# diskohedron4w_pinheaders.net
KiCad netlist of a schematic drawn in EAGLE
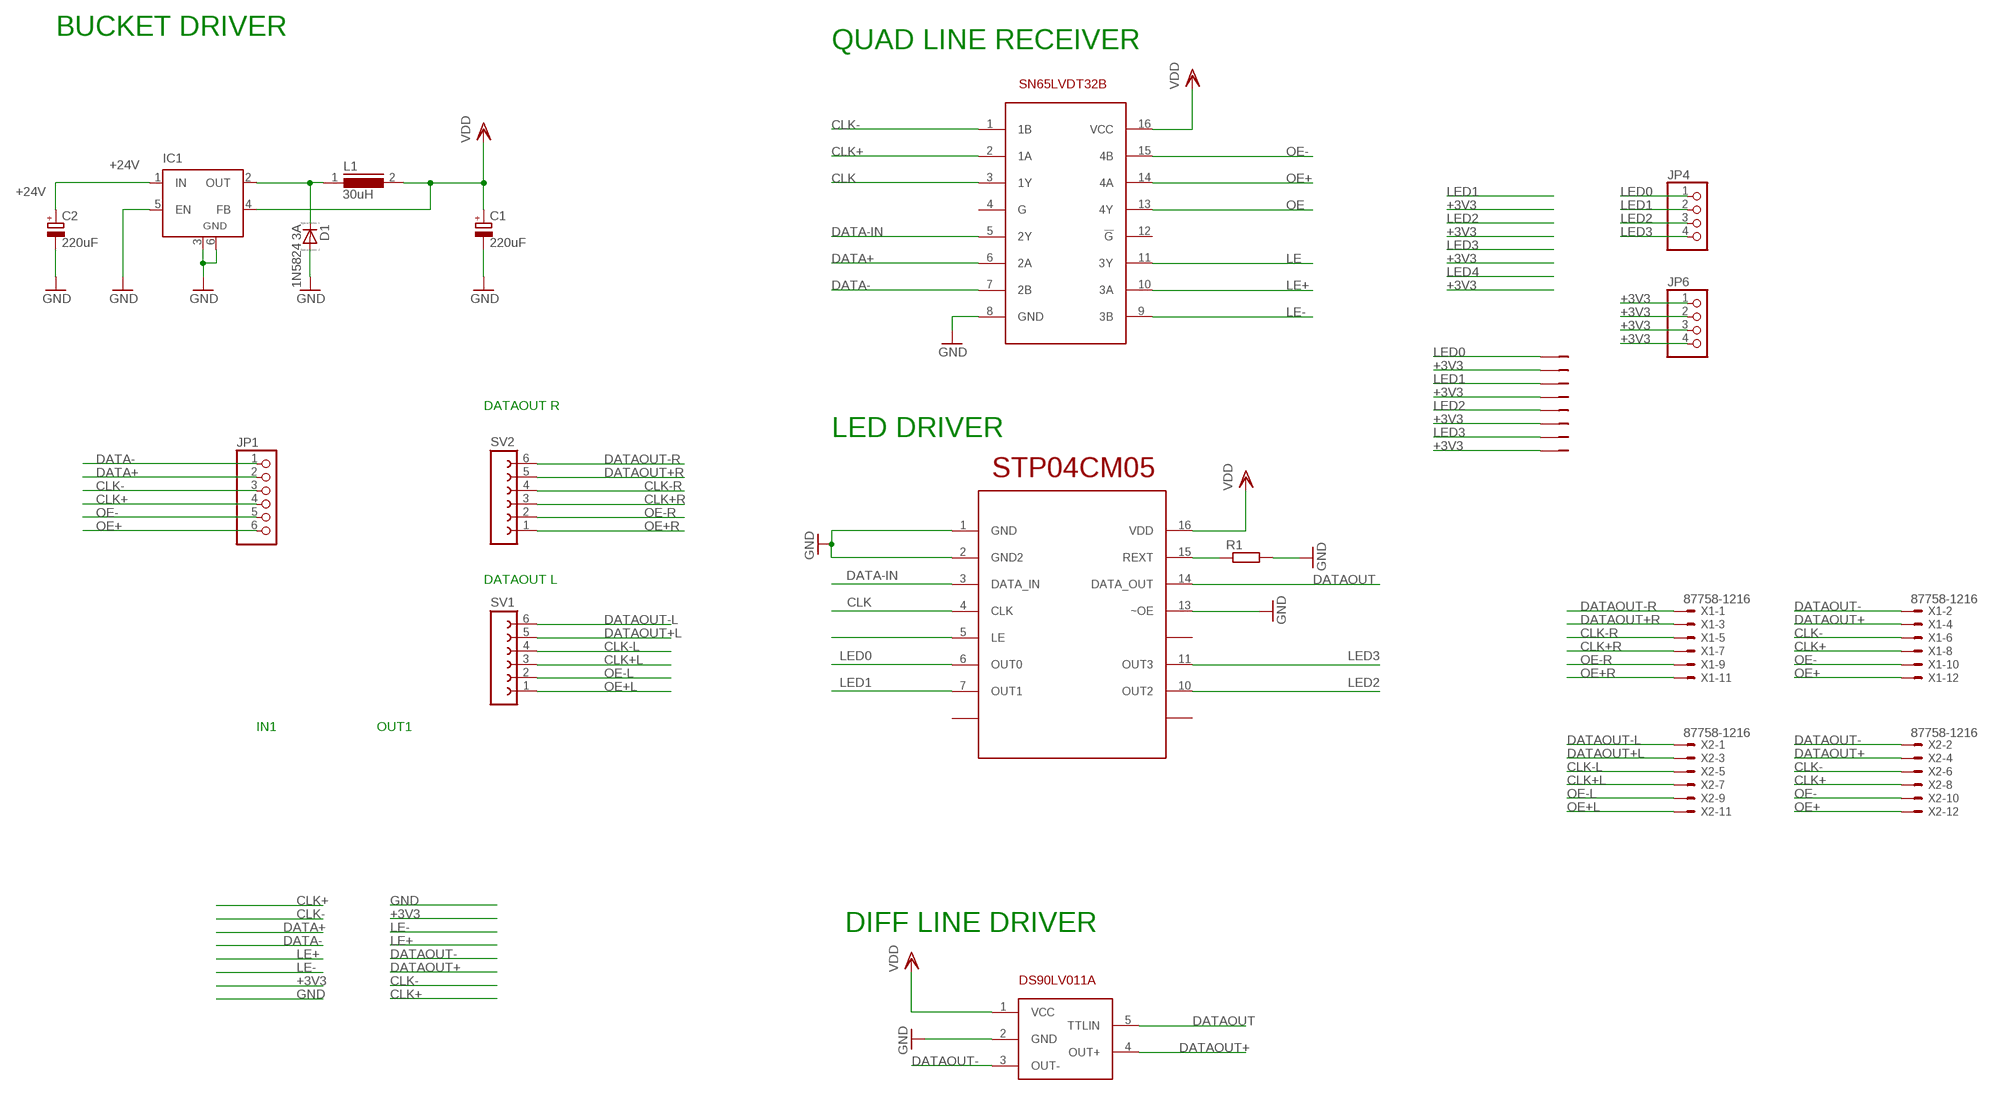
[diagram p0: schematic, sheet 1]

(export (version "E")
  (design (tool "Eeschema 10.0.6"))
  (components
    (comp (ref "C1")
      (value "220uF")
      (footprint "eagle-import:153CLV-1010")
      (libsource (lib "eagle-import") (part "CPOL-EU153CLV-1010"))
    )
    (comp (ref "C2")
      (value "220uF")
      (footprint "eagle-import:153CLV-1010")
      (libsource (lib "eagle-import") (part "CPOL-EU153CLV-1010"))
    )
    (comp (ref "D1")
      (value "1N5824 3A")
      (footprint "eagle-import:DIODE_SMC")
      (libsource (lib "eagle-import") (part "DIODE_E-SMC"))
    )
    (comp (ref "IC1")
      (value "LM2596S")
      (footprint "eagle-import:TO263-5")
      (libsource (lib "eagle-import") (part "LM2596S"))
    )
    (comp (ref "JP1")
      (value "PINHD-1X06_2.54-90°")
      (footprint "eagle-import:1X06_90")
      (libsource (lib "eagle-import") (part "PINHD-1X06_2.54-90°"))
    )
    (comp (ref "JP4")
      (value "PINHD-1X4")
      (footprint "eagle-import:1X04")
      (libsource (lib "eagle-import") (part "PINHD-1X4"))
    )
    (comp (ref "JP6")
      (value "PINHD-1X4")
      (footprint "eagle-import:1X04")
      (libsource (lib "eagle-import") (part "PINHD-1X4"))
    )
    (comp (ref "L1")
      (value "30uH")
      (footprint "eagle-import:DR127")
      (libsource (lib "eagle-import") (part "DR127"))
    )
    (comp (ref "R1")
      (value "R-EU_M0805")
      (footprint "eagle-import:M0805")
      (libsource (lib "eagle-import") (part "R-EU_M0805"))
    )
    (comp (ref "SV1")
      (value "FE06W")
      (footprint "eagle-import:FE06W")
      (libsource (lib "eagle-import") (part "FE06W"))
    )
    (comp (ref "SV2")
      (value "FE06W")
      (footprint "eagle-import:FE06W")
      (libsource (lib "eagle-import") (part "FE06W"))
    )
    (comp (ref "U$1")
      (value "STP04CM05")
      (footprint "eagle-import:TSSOP16")
      (libsource (lib "eagle-import") (part "STP04CM05"))
    )
    (comp (ref "U$2")
      (value "SN65LVDST32")
      (footprint "eagle-import:SOIC16")
      (libsource (lib "eagle-import") (part "SN65LVDST32"))
    )
    (comp (ref "U$3")
      (value "DS90LV011A")
      (footprint "eagle-import:SOT23-5")
      (libsource (lib "eagle-import") (part "DS90LV011A"))
    )
    (comp (ref "U$4")
      (value "8PIN-ZH")
      (footprint "eagle-import:B8B-ZH")
      (libsource (lib "eagle-import") (part "8PIN-ZH"))
    )
    (comp (ref "X1")
      (value "87758-1216")
      (footprint "eagle-import:87758-1216")
      (libsource (lib "eagle-import") (part "87758-1216"))
    )
    (comp (ref "X2")
      (value "87758-1216")
      (footprint "eagle-import:87758-1216")
      (libsource (lib "eagle-import") (part "87758-1216"))
    )
  )
  (nets
    (net (code "1") (name "/+24V") (class "Default")
      (node (ref "C2") (pin "+") (pinfunction "+_+") (pintype "passive"))
      (node (ref "IC1") (pin "1") (pinfunction "IN_1") (pintype "input"))
    )
    (net (code "2") (name "/CLK") (class "Default")
      (node (ref "U$1") (pin "4") (pinfunction "CLK_4") (pintype "bidirectional"))
      (node (ref "U$2") (pin "3") (pinfunction "1Y_3") (pintype "bidirectional"))
    )
    (net (code "3") (name "/CLK+") (class "Default")
      (node (ref "JP1") (pin "4") (pinfunction "4_4") (pintype "passive"))
      (node (ref "U$2") (pin "2") (pinfunction "1A_2") (pintype "bidirectional"))
      (node (ref "X1") (pin "8") (pinfunction "S_8") (pintype "passive"))
      (node (ref "X2") (pin "8") (pinfunction "S_8") (pintype "passive"))
    )
    (net (code "4") (name "/CLK+L") (class "Default")
      (node (ref "SV1") (pin "3") (pinfunction "3_3") (pintype "passive"))
      (node (ref "X2") (pin "7") (pinfunction "S_7") (pintype "passive"))
    )
    (net (code "5") (name "/CLK+R") (class "Default")
      (node (ref "SV2") (pin "3") (pinfunction "3_3") (pintype "passive"))
      (node (ref "X1") (pin "7") (pinfunction "S_7") (pintype "passive"))
    )
    (net (code "6") (name "/CLK-") (class "Default")
      (node (ref "JP1") (pin "3") (pinfunction "3_3") (pintype "passive"))
      (node (ref "U$2") (pin "1") (pinfunction "1B_1") (pintype "bidirectional"))
      (node (ref "X1") (pin "6") (pinfunction "S_6") (pintype "passive"))
      (node (ref "X2") (pin "6") (pinfunction "S_6") (pintype "passive"))
    )
    (net (code "7") (name "/CLK-L") (class "Default")
      (node (ref "SV1") (pin "4") (pinfunction "4_4") (pintype "passive"))
      (node (ref "X2") (pin "5") (pinfunction "S_5") (pintype "passive"))
    )
    (net (code "8") (name "/CLK-R") (class "Default")
      (node (ref "SV2") (pin "4") (pinfunction "4_4") (pintype "passive"))
      (node (ref "X1") (pin "5") (pinfunction "S_5") (pintype "passive"))
    )
    (net (code "9") (name "/DATA+") (class "Default")
      (node (ref "JP1") (pin "2") (pinfunction "2_2") (pintype "passive"))
      (node (ref "U$2") (pin "6") (pinfunction "2A_6") (pintype "bidirectional"))
    )
    (net (code "10") (name "/DATA-") (class "Default")
      (node (ref "JP1") (pin "1") (pinfunction "1_1") (pintype "passive"))
      (node (ref "U$2") (pin "7") (pinfunction "2B_7") (pintype "bidirectional"))
    )
    (net (code "11") (name "/DATA-IN") (class "Default")
      (node (ref "U$1") (pin "3") (pinfunction "DATA_IN_3") (pintype "bidirectional"))
      (node (ref "U$2") (pin "5") (pinfunction "2Y_5") (pintype "bidirectional"))
    )
    (net (code "12") (name "/DATAOUT") (class "Default")
      (node (ref "U$1") (pin "14") (pinfunction "DATA_OUT_14") (pintype "bidirectional"))
      (node (ref "U$3") (pin "5") (pinfunction "TTLIN_5") (pintype "bidirectional"))
    )
    (net (code "13") (name "/DATAOUT+") (class "Default")
      (node (ref "U$3") (pin "4") (pinfunction "OUT+_4") (pintype "bidirectional"))
      (node (ref "X1") (pin "4") (pinfunction "S_4") (pintype "passive"))
      (node (ref "X2") (pin "4") (pinfunction "S_4") (pintype "passive"))
    )
    (net (code "14") (name "/DATAOUT+L") (class "Default")
      (node (ref "SV1") (pin "5") (pinfunction "5_5") (pintype "passive"))
      (node (ref "X2") (pin "3") (pinfunction "S_3") (pintype "passive"))
    )
    (net (code "15") (name "/DATAOUT+R") (class "Default")
      (node (ref "SV2") (pin "5") (pinfunction "5_5") (pintype "passive"))
      (node (ref "X1") (pin "3") (pinfunction "S_3") (pintype "passive"))
    )
    (net (code "16") (name "/DATAOUT-") (class "Default")
      (node (ref "U$3") (pin "3") (pinfunction "OUT-_3") (pintype "bidirectional"))
      (node (ref "X1") (pin "2") (pinfunction "S_2") (pintype "passive"))
      (node (ref "X2") (pin "2") (pinfunction "S_2") (pintype "passive"))
    )
    (net (code "17") (name "/DATAOUT-L") (class "Default")
      (node (ref "SV1") (pin "6") (pinfunction "6_6") (pintype "passive"))
      (node (ref "X2") (pin "1") (pinfunction "S_1") (pintype "passive"))
    )
    (net (code "18") (name "/DATAOUT-R") (class "Default")
      (node (ref "SV2") (pin "6") (pinfunction "6_6") (pintype "passive"))
      (node (ref "X1") (pin "1") (pinfunction "S_1") (pintype "passive"))
    )
    (net (code "19") (name "/LE") (class "Default")
      (node (ref "U$1") (pin "5") (pinfunction "LE_5") (pintype "bidirectional"))
      (node (ref "U$2") (pin "11") (pinfunction "3Y_11") (pintype "bidirectional"))
    )
    (net (code "20") (name "/LE+") (class "Default")
      (node (ref "U$2") (pin "10") (pinfunction "3A_10") (pintype "bidirectional"))
    )
    (net (code "21") (name "/LE-") (class "Default")
      (node (ref "U$2") (pin "9") (pinfunction "3B_9") (pintype "bidirectional"))
    )
    (net (code "22") (name "/LED0") (class "Default")
      (node (ref "JP4") (pin "1") (pinfunction "1_1") (pintype "passive"))
      (node (ref "U$1") (pin "6") (pinfunction "OUT0_6") (pintype "bidirectional"))
      (node (ref "U$4") (pin "1") (pinfunction "1_1") (pintype "passive"))
    )
    (net (code "23") (name "/LED1") (class "Default")
      (node (ref "JP4") (pin "2") (pinfunction "2_2") (pintype "passive"))
      (node (ref "U$1") (pin "7") (pinfunction "OUT1_7") (pintype "bidirectional"))
      (node (ref "U$4") (pin "3") (pinfunction "1_3") (pintype "passive"))
    )
    (net (code "24") (name "/LED2") (class "Default")
      (node (ref "JP4") (pin "3") (pinfunction "3_3") (pintype "passive"))
      (node (ref "U$1") (pin "10") (pinfunction "OUT2_10") (pintype "bidirectional"))
      (node (ref "U$4") (pin "5") (pinfunction "1_5") (pintype "passive"))
    )
    (net (code "25") (name "/LED3") (class "Default")
      (node (ref "JP4") (pin "4") (pinfunction "4_4") (pintype "passive"))
      (node (ref "U$1") (pin "11") (pinfunction "OUT3_11") (pintype "bidirectional"))
      (node (ref "U$4") (pin "7") (pinfunction "1_7") (pintype "passive"))
    )
    (net (code "27") (name "/OE") (class "Default")
      (node (ref "U$2") (pin "13") (pinfunction "4Y_13") (pintype "bidirectional"))
    )
    (net (code "28") (name "/OE+") (class "Default")
      (node (ref "JP1") (pin "6") (pinfunction "6_6") (pintype "passive"))
      (node (ref "U$2") (pin "14") (pinfunction "4A_14") (pintype "bidirectional"))
      (node (ref "X1") (pin "12") (pinfunction "S_12") (pintype "passive"))
      (node (ref "X2") (pin "12") (pinfunction "S_12") (pintype "passive"))
    )
    (net (code "29") (name "/OE+L") (class "Default")
      (node (ref "SV1") (pin "1") (pinfunction "1_1") (pintype "passive"))
      (node (ref "X2") (pin "11") (pinfunction "S_11") (pintype "passive"))
    )
    (net (code "30") (name "/OE+R") (class "Default")
      (node (ref "SV2") (pin "1") (pinfunction "1_1") (pintype "passive"))
      (node (ref "X1") (pin "11") (pinfunction "S_11") (pintype "passive"))
    )
    (net (code "31") (name "/OE-") (class "Default")
      (node (ref "JP1") (pin "5") (pinfunction "5_5") (pintype "passive"))
      (node (ref "U$2") (pin "15") (pinfunction "4B_15") (pintype "bidirectional"))
      (node (ref "X1") (pin "10") (pinfunction "S_10") (pintype "passive"))
      (node (ref "X2") (pin "10") (pinfunction "S_10") (pintype "passive"))
    )
    (net (code "32") (name "/OE-L") (class "Default")
      (node (ref "SV1") (pin "2") (pinfunction "2_2") (pintype "passive"))
      (node (ref "X2") (pin "9") (pinfunction "S_9") (pintype "passive"))
    )
    (net (code "33") (name "/OE-R") (class "Default")
      (node (ref "SV2") (pin "2") (pinfunction "2_2") (pintype "passive"))
      (node (ref "X1") (pin "9") (pinfunction "S_9") (pintype "passive"))
    )
    (net (code "34") (name "GND") (class "Default")
      (node (ref "C1") (pin "-") (pinfunction "-_-") (pintype "passive"))
      (node (ref "C2") (pin "-") (pinfunction "-_-") (pintype "passive"))
      (node (ref "D1") (pin "A") (pinfunction "C_A") (pintype "passive"))
      (node (ref "IC1") (pin "3") (pinfunction "GND_3") (pintype "power_in"))
      (node (ref "IC1") (pin "5") (pinfunction "EN_5") (pintype "input"))
      (node (ref "IC1") (pin "6") (pinfunction "GND_6") (pintype "power_in"))
      (node (ref "R1") (pin "2") (pinfunction "2_2") (pintype "passive"))
      (node (ref "U$1") (pin "1") (pinfunction "GND_1") (pintype "bidirectional"))
      (node (ref "U$1") (pin "13") (pinfunction "~{OE}_13") (pintype "bidirectional"))
      (node (ref "U$1") (pin "2") (pinfunction "GND2_2") (pintype "bidirectional"))
      (node (ref "U$2") (pin "8") (pinfunction "GND_8") (pintype "bidirectional"))
      (node (ref "U$3") (pin "2") (pinfunction "GND_2") (pintype "bidirectional"))
    )
    (net (code "35") (name "Net-(D1-A)") (class "Default")
      (node (ref "D1") (pin "C") (pinfunction "A_C") (pintype "passive"))
      (node (ref "IC1") (pin "2") (pinfunction "OUT_2") (pintype "output"))
      (node (ref "L1") (pin "1") (pinfunction "1_1") (pintype "passive"))
    )
    (net (code "36") (name "Net-(U$1-REXT)") (class "Default")
      (node (ref "R1") (pin "1") (pinfunction "1_1") (pintype "passive"))
      (node (ref "U$1") (pin "15") (pinfunction "REXT_15") (pintype "bidirectional"))
    )
    (net (code "37") (name "VDD") (class "Default")
      (node (ref "C1") (pin "+") (pinfunction "+_+") (pintype "passive"))
      (node (ref "IC1") (pin "4") (pinfunction "FB_4") (pintype "input"))
      (node (ref "JP6") (pin "1") (pinfunction "1_1") (pintype "passive"))
      (node (ref "JP6") (pin "2") (pinfunction "2_2") (pintype "passive"))
      (node (ref "JP6") (pin "3") (pinfunction "3_3") (pintype "passive"))
      (node (ref "JP6") (pin "4") (pinfunction "4_4") (pintype "passive"))
      (node (ref "L1") (pin "2") (pinfunction "2_2") (pintype "passive"))
      (node (ref "U$1") (pin "16") (pinfunction "VDD_16") (pintype "bidirectional"))
      (node (ref "U$2") (pin "16") (pinfunction "VCC_16") (pintype "bidirectional"))
      (node (ref "U$3") (pin "1") (pinfunction "VCC_1") (pintype "bidirectional"))
      (node (ref "U$4") (pin "2") (pinfunction "1_2") (pintype "passive"))
      (node (ref "U$4") (pin "4") (pinfunction "1_4") (pintype "passive"))
      (node (ref "U$4") (pin "6") (pinfunction "1_6") (pintype "passive"))
      (node (ref "U$4") (pin "8") (pinfunction "1_8") (pintype "passive"))
    )
    (net (code "38") (name "unconnected-(U$1-N.C1-Pad8)") (class "Default")
      (node (ref "U$1") (pin "8") (pinfunction "N.C1_8") (pintype "bidirectional"))
    )
    (net (code "39") (name "unconnected-(U$1-NC-Pad9)") (class "Default")
      (node (ref "U$1") (pin "9") (pinfunction "NC_9") (pintype "bidirectional"))
    )
    (net (code "40") (name "unconnected-(U$1-NC3-Pad12)") (class "Default")
      (node (ref "U$1") (pin "12") (pinfunction "NC3_12") (pintype "bidirectional"))
    )
    (net (code "41") (name "unconnected-(U$2-G-Pad4)") (class "Default")
      (node (ref "U$2") (pin "4") (pinfunction "G_4") (pintype "bidirectional"))
    )
    (net (code "42") (name "unconnected-(U$2-~{G}-Pad12)") (class "Default")
      (node (ref "U$2") (pin "12") (pinfunction "~{G}_12") (pintype "bidirectional"))
    )
  )
)
